# motor_output.net
KiCad netlist of a schematic drawn in Altium Designer
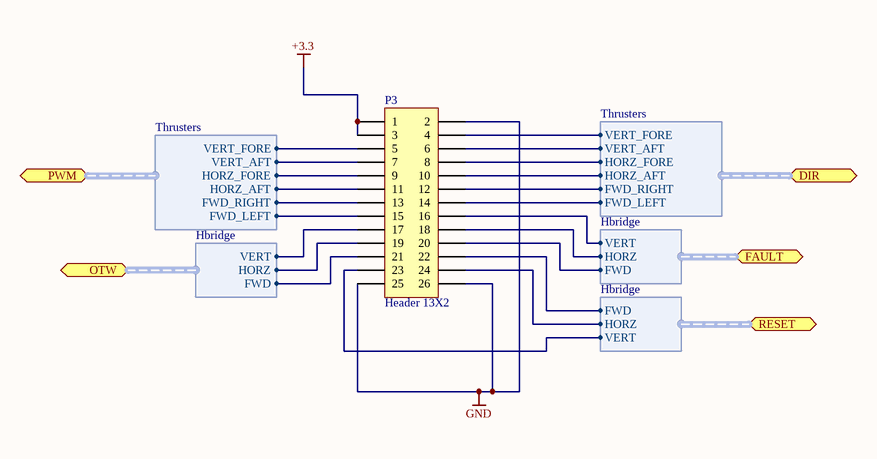
[diagram p0: motor_output.SchDoc]

(export (version "E")
  (design (tool "Eeschema 10.0.6"))
  (components
    (comp (ref "P3")
      (value "Header 13X2")
      (footprint "HDR2X13")
      (description "Header, 13-Pin, Dual row")
      (fields (field (name "PUBLISHER") "Altium Limited"))
      (libsource (lib "Miscellaneous Connectors") (part "Header 13X2"))
    )
  )
  (nets
    (net (code "3") (name "+3.3") (class "Default")
      (node (ref "P3") (pin "1") (pinfunction "1_1") (pintype "passive"))
      (node (ref "P3") (pin "3") (pinfunction "3_3") (pintype "passive"))
    )
    (net (code "6") (name "GND") (class "Default")
      (node (ref "P3") (pin "2") (pinfunction "2_2") (pintype "passive"))
      (node (ref "P3") (pin "25") (pinfunction "25_25") (pintype "passive"))
      (node (ref "P3") (pin "26") (pinfunction "26_26") (pintype "passive"))
    )
    (net (code "7") (name "unconnected-(P3-Pad4)") (class "Default")
      (node (ref "P3") (pin "4") (pinfunction "4_4") (pintype "passive"))
    )
    (net (code "8") (name "unconnected-(P3-Pad5)") (class "Default")
      (node (ref "P3") (pin "5") (pinfunction "5_5") (pintype "passive"))
    )
    (net (code "9") (name "unconnected-(P3-Pad6)") (class "Default")
      (node (ref "P3") (pin "6") (pinfunction "6_6") (pintype "passive"))
    )
    (net (code "10") (name "unconnected-(P3-Pad7)") (class "Default")
      (node (ref "P3") (pin "7") (pinfunction "7_7") (pintype "passive"))
    )
    (net (code "11") (name "unconnected-(P3-Pad8)") (class "Default")
      (node (ref "P3") (pin "8") (pinfunction "8_8") (pintype "passive"))
    )
    (net (code "12") (name "unconnected-(P3-Pad9)") (class "Default")
      (node (ref "P3") (pin "9") (pinfunction "9_9") (pintype "passive"))
    )
    (net (code "13") (name "unconnected-(P3-Pad10)") (class "Default")
      (node (ref "P3") (pin "10") (pinfunction "10_10") (pintype "passive"))
    )
    (net (code "14") (name "unconnected-(P3-Pad11)") (class "Default")
      (node (ref "P3") (pin "11") (pinfunction "11_11") (pintype "passive"))
    )
    (net (code "15") (name "unconnected-(P3-Pad12)") (class "Default")
      (node (ref "P3") (pin "12") (pinfunction "12_12") (pintype "passive"))
    )
    (net (code "16") (name "unconnected-(P3-Pad13)") (class "Default")
      (node (ref "P3") (pin "13") (pinfunction "13_13") (pintype "passive"))
    )
    (net (code "17") (name "unconnected-(P3-Pad14)") (class "Default")
      (node (ref "P3") (pin "14") (pinfunction "14_14") (pintype "passive"))
    )
    (net (code "18") (name "unconnected-(P3-Pad15)") (class "Default")
      (node (ref "P3") (pin "15") (pinfunction "15_15") (pintype "passive"))
    )
    (net (code "19") (name "unconnected-(P3-Pad16)") (class "Default")
      (node (ref "P3") (pin "16") (pinfunction "16_16") (pintype "passive"))
    )
    (net (code "20") (name "unconnected-(P3-Pad17)") (class "Default")
      (node (ref "P3") (pin "17") (pinfunction "17_17") (pintype "passive"))
    )
    (net (code "21") (name "unconnected-(P3-Pad18)") (class "Default")
      (node (ref "P3") (pin "18") (pinfunction "18_18") (pintype "passive"))
    )
    (net (code "22") (name "unconnected-(P3-Pad19)") (class "Default")
      (node (ref "P3") (pin "19") (pinfunction "19_19") (pintype "passive"))
    )
    (net (code "23") (name "unconnected-(P3-Pad20)") (class "Default")
      (node (ref "P3") (pin "20") (pinfunction "20_20") (pintype "passive"))
    )
    (net (code "24") (name "unconnected-(P3-Pad21)") (class "Default")
      (node (ref "P3") (pin "21") (pinfunction "21_21") (pintype "passive"))
    )
    (net (code "25") (name "unconnected-(P3-Pad22)") (class "Default")
      (node (ref "P3") (pin "22") (pinfunction "22_22") (pintype "passive"))
    )
    (net (code "26") (name "unconnected-(P3-Pad23)") (class "Default")
      (node (ref "P3") (pin "23") (pinfunction "23_23") (pintype "passive"))
    )
    (net (code "27") (name "unconnected-(P3-Pad24)") (class "Default")
      (node (ref "P3") (pin "24") (pinfunction "24_24") (pintype "passive"))
    )
  )
)
